# SCH_NFC-Business-Card1_2025-01-03.net
KiCad netlist of a schematic drawn in EasyEDA
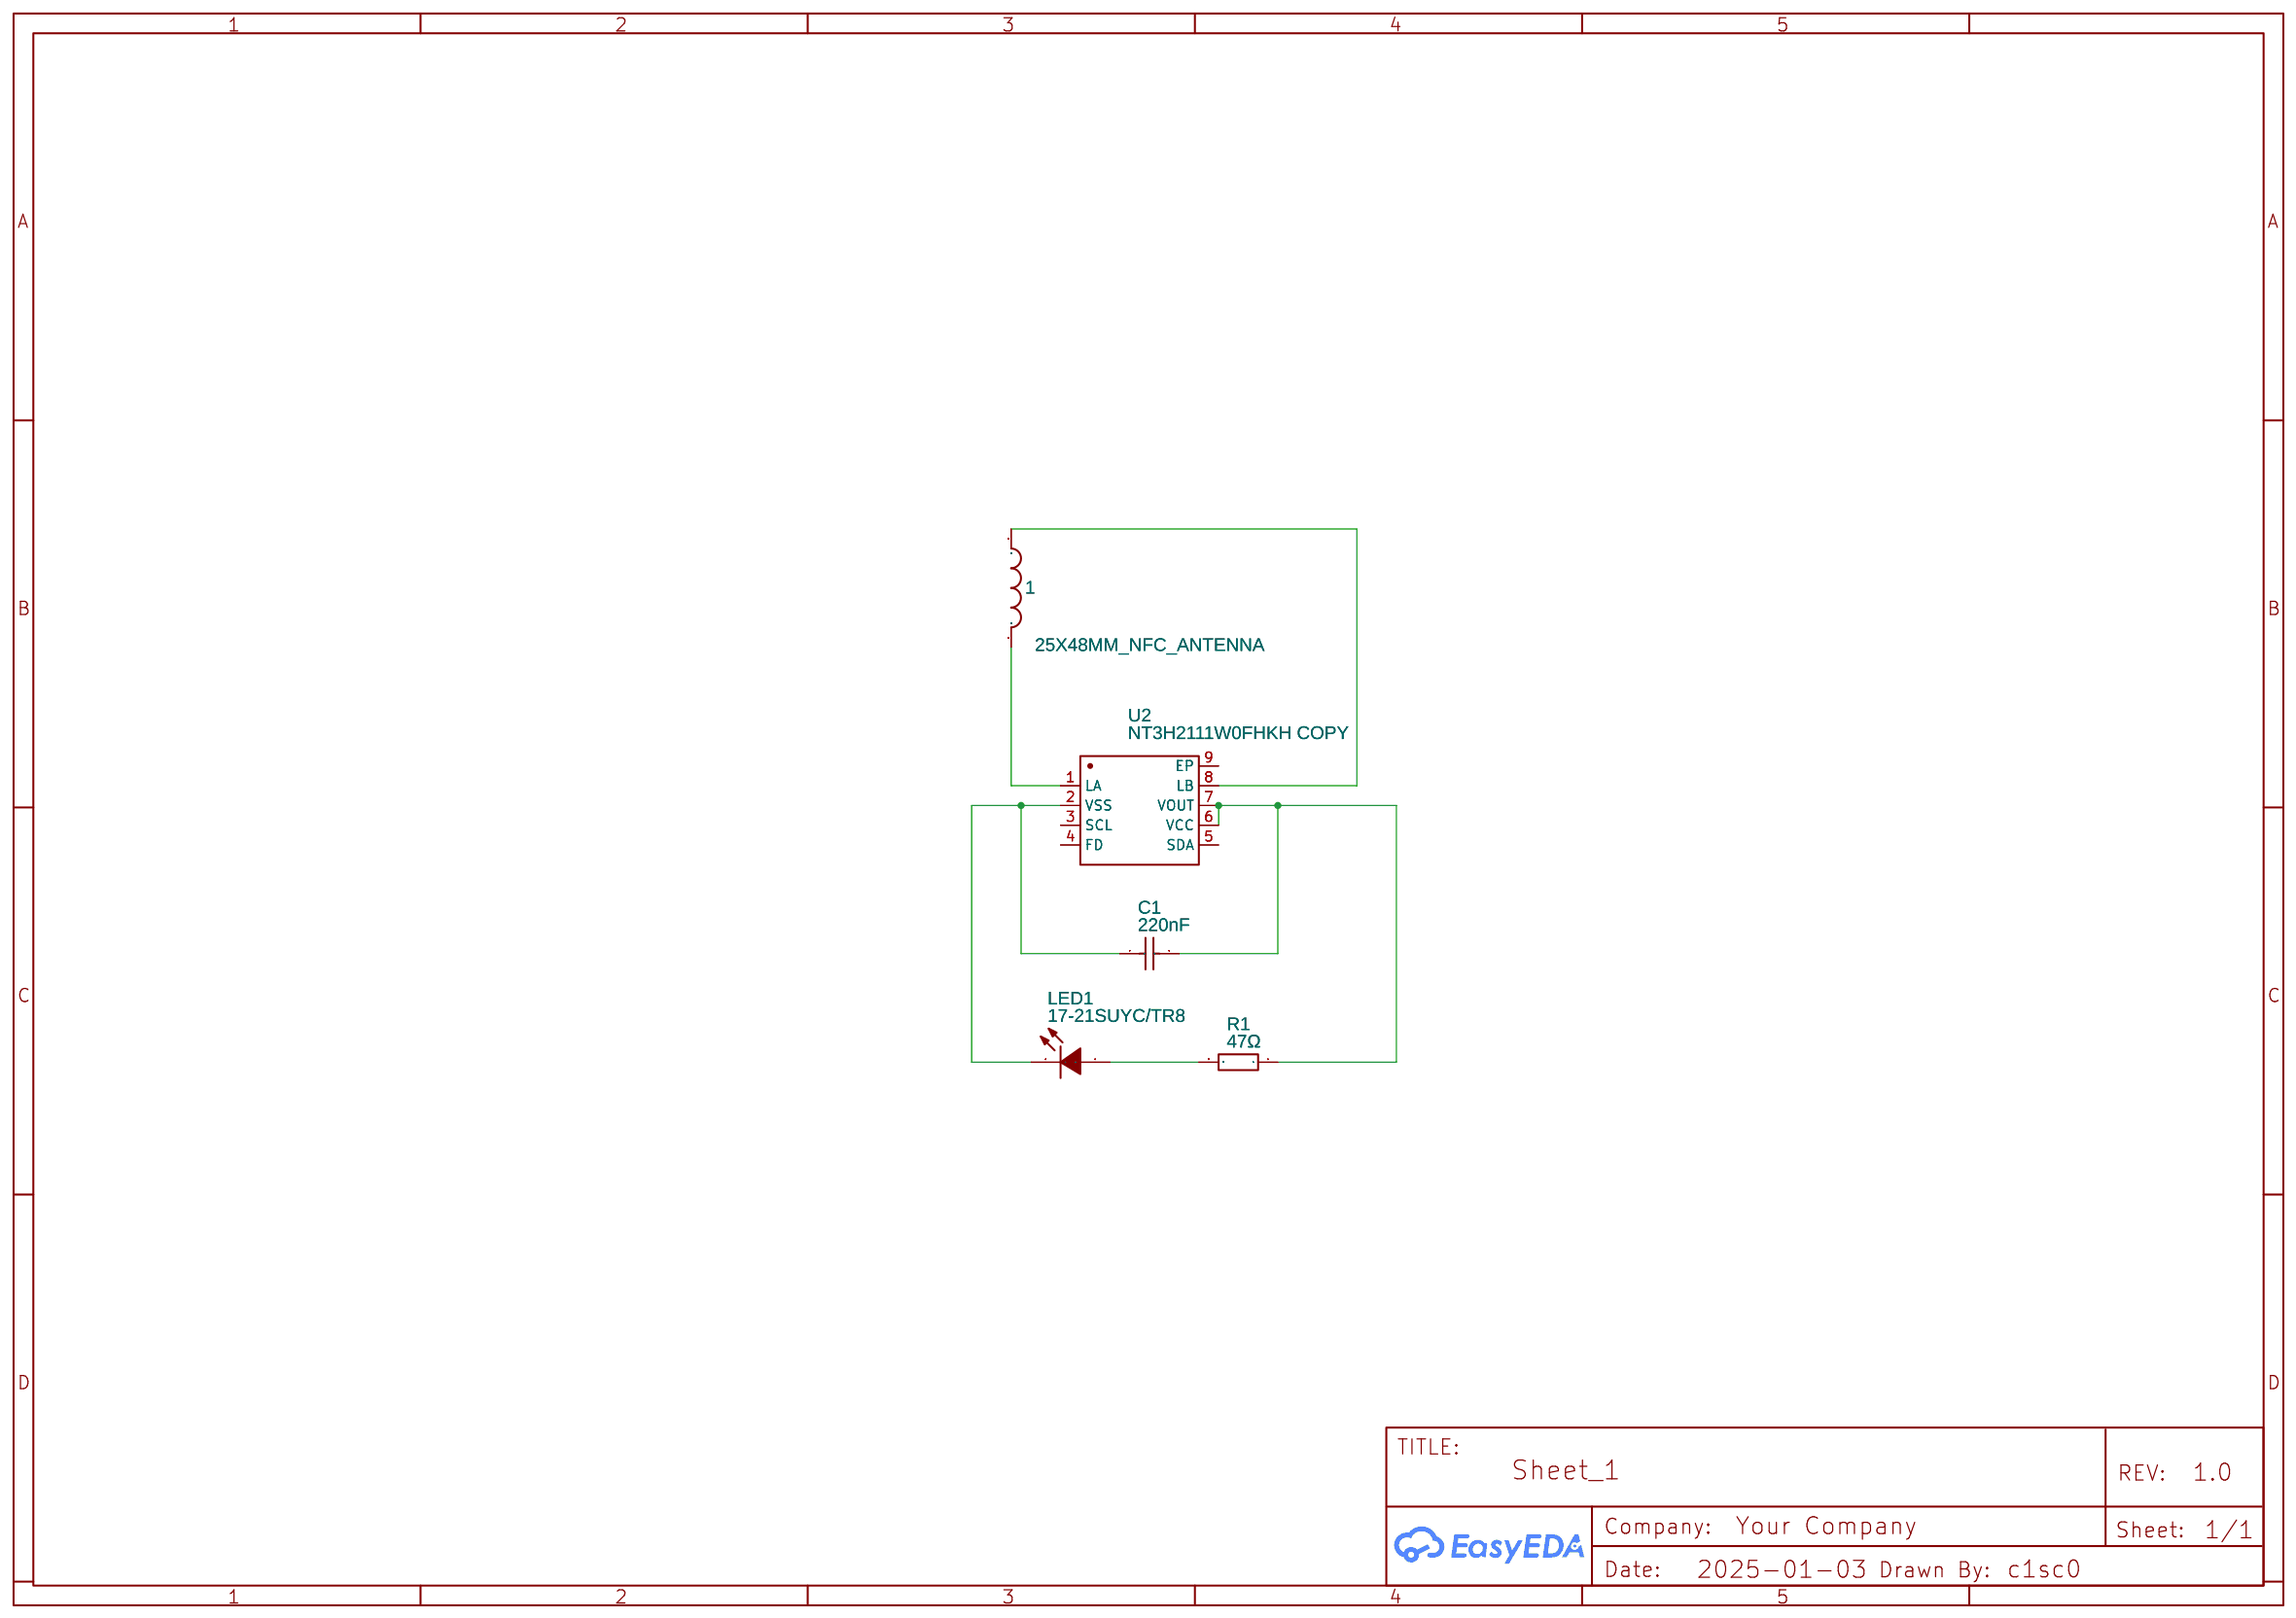
[diagram p0: schematic sheet]

(export (version "E")
  (design (tool "Eeschema 10.0.6"))
  (components
    (comp (ref "1") (value "25X48MM_NFC_ANTENNA") (libsource (lib "") (part "25X48MM_NFC_ANTENNA")))
    (comp (ref "C1")
      (value "220nF")
      (fields
        (field (name "Manufacturer Part") "CL10B224KA8NNNC")
        (field (name "Manufacturer") "SAMSUNG(三星)")
      )
      (libsource (lib "") (part "CL10B224KA8NNNC"))
    )
    (comp (ref "LED1")
      (value "17-21SUYC/TR8")
      (fields (field (name "Manufacturer Part") "KT-0805黄灯") (field (name "Manufacturer") "KENTO"))
      (libsource (lib "") (part "17-21SUYC/TR8"))
    )
    (comp (ref "R1")
      (value "47Ω")
      (fields
        (field (name "Manufacturer Part") "0603WAF470JT5E")
        (field (name "Manufacturer") "UNI-ROYAL(厚声)")
      )
      (libsource (lib "") (part "0603WAF470JT5E"))
    )
    (comp (ref "U2")
      (value "NT3H2111W0FHKH COPY")
      (fields (field (name "Manufacturer Part") "NT3H2111W0FHKH") (field (name "Manufacturer") "NXP(恩智浦)"))
      (libsource (lib "") (part "NT3H2111W0FHKH COPY"))
    )
  )
  (nets
    (net (code "1") (name "Net-(LED1-+)") (class "Default")
      (node (ref "LED1") (pin "1") (pinfunction "+_1") (pintype "unspecified"))
      (node (ref "R1") (pin "2") (pinfunction "2_2") (pintype "input"))
    )
    (net (code "2") (name "Net-(LED1--)") (class "Default")
      (node (ref "C1") (pin "1") (pinfunction "1_1") (pintype "input"))
      (node (ref "LED1") (pin "2") (pinfunction "-_2") (pintype "unspecified"))
      (node (ref "U2") (pin "2") (pinfunction "VSS_2") (pintype "unspecified"))
    )
    (net (code "3") (name "Net-(U2-LA)") (class "Default")
      (node (ref "1") (pin "P$2") (pinfunction "P$2_P$2") (pintype "bidirectional"))
      (node (ref "U2") (pin "1") (pinfunction "LA_1") (pintype "unspecified"))
    )
    (net (code "4") (name "Net-(U2-LB)") (class "Default")
      (node (ref "1") (pin "P$1") (pinfunction "P$1_P$1") (pintype "bidirectional"))
      (node (ref "U2") (pin "8") (pinfunction "LB_8") (pintype "unspecified"))
    )
    (net (code "5") (name "Net-(U2-VCC)") (class "Default")
      (node (ref "C1") (pin "2") (pinfunction "2_2") (pintype "input"))
      (node (ref "R1") (pin "1") (pinfunction "1_1") (pintype "input"))
      (node (ref "U2") (pin "6") (pinfunction "VCC_6") (pintype "unspecified"))
      (node (ref "U2") (pin "7") (pinfunction "VOUT_7") (pintype "unspecified"))
    )
    (net (code "6") (name "unconnected-(U2-EP-Pad9)") (class "Default")
      (node (ref "U2") (pin "9") (pinfunction "EP_9") (pintype "unspecified"))
    )
    (net (code "7") (name "unconnected-(U2-FD-Pad4)") (class "Default")
      (node (ref "U2") (pin "4") (pinfunction "FD_4") (pintype "unspecified"))
    )
    (net (code "8") (name "unconnected-(U2-SCL-Pad3)") (class "Default")
      (node (ref "U2") (pin "3") (pinfunction "SCL_3") (pintype "unspecified"))
    )
    (net (code "9") (name "unconnected-(U2-SDA-Pad5)") (class "Default")
      (node (ref "U2") (pin "5") (pinfunction "SDA_5") (pintype "unspecified"))
    )
  )
)
